# SensorU.net
KiCad netlist of a schematic drawn in EAGLE
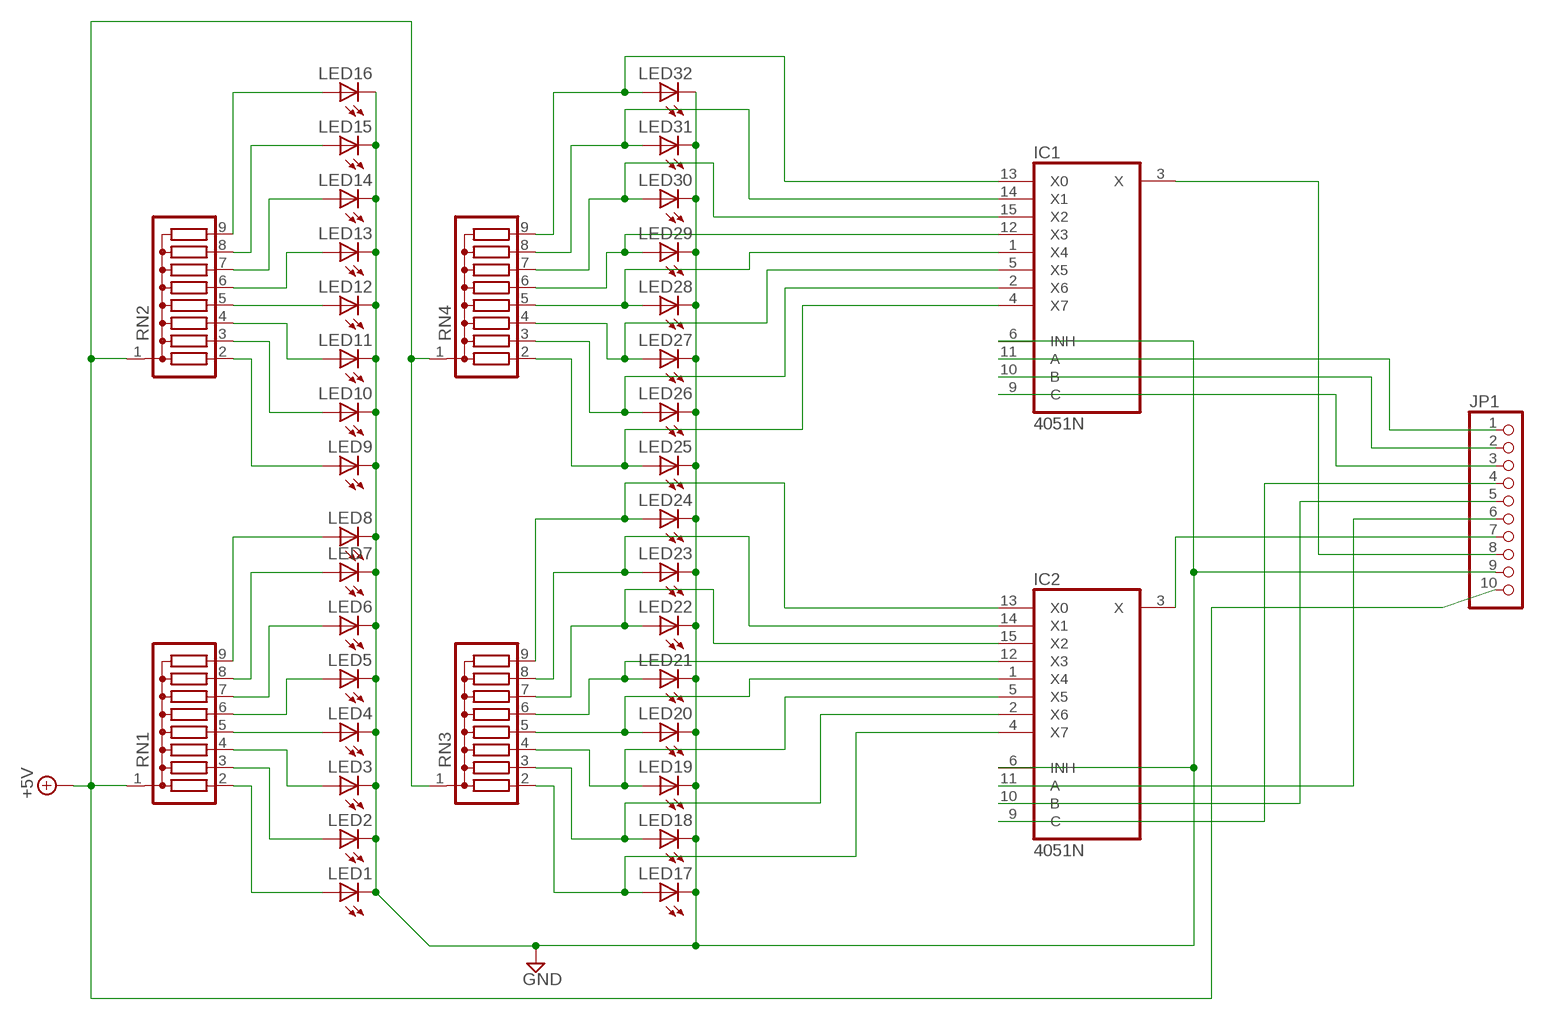
[diagram p0: schematic, sheet 1]

(export (version "E")
  (design (tool "Eeschema 10.0.6"))
  (components
    (comp (ref "IC1")
      (value "4051N")
      (footprint "eagle-import:DIL16")
      (libsource (lib "eagle-import") (part "4051N"))
    )
    (comp (ref "IC2")
      (value "4051N")
      (footprint "eagle-import:DIL16")
      (libsource (lib "eagle-import") (part "4051N"))
    )
    (comp (ref "JP1")
      (value "PINHD-1X10")
      (footprint "eagle-import:1X10")
      (libsource (lib "eagle-import") (part "PINHD-1X10"))
    )
    (comp (ref "LED1")
      (value "LED3MM")
      (footprint "eagle-import:LED3MM")
      (libsource (lib "eagle-import") (part "LED3MM"))
    )
    (comp (ref "LED2")
      (value "LED3MM")
      (footprint "eagle-import:LED3MM")
      (libsource (lib "eagle-import") (part "LED3MM"))
    )
    (comp (ref "LED3")
      (value "LED3MM")
      (footprint "eagle-import:LED3MM")
      (libsource (lib "eagle-import") (part "LED3MM"))
    )
    (comp (ref "LED4")
      (value "LED3MM")
      (footprint "eagle-import:LED3MM")
      (libsource (lib "eagle-import") (part "LED3MM"))
    )
    (comp (ref "LED5")
      (value "LED3MM")
      (footprint "eagle-import:LED3MM")
      (libsource (lib "eagle-import") (part "LED3MM"))
    )
    (comp (ref "LED6")
      (value "LED3MM")
      (footprint "eagle-import:LED3MM")
      (libsource (lib "eagle-import") (part "LED3MM"))
    )
    (comp (ref "LED7")
      (value "LED3MM")
      (footprint "eagle-import:LED3MM")
      (libsource (lib "eagle-import") (part "LED3MM"))
    )
    (comp (ref "LED8")
      (value "LED3MM")
      (footprint "eagle-import:LED3MM")
      (libsource (lib "eagle-import") (part "LED3MM"))
    )
    (comp (ref "LED9")
      (value "LED3MM")
      (footprint "eagle-import:LED3MM")
      (libsource (lib "eagle-import") (part "LED3MM"))
    )
    (comp (ref "LED10")
      (value "LED3MM")
      (footprint "eagle-import:LED3MM")
      (libsource (lib "eagle-import") (part "LED3MM"))
    )
    (comp (ref "LED11")
      (value "LED3MM")
      (footprint "eagle-import:LED3MM")
      (libsource (lib "eagle-import") (part "LED3MM"))
    )
    (comp (ref "LED12")
      (value "LED3MM")
      (footprint "eagle-import:LED3MM")
      (libsource (lib "eagle-import") (part "LED3MM"))
    )
    (comp (ref "LED13")
      (value "LED3MM")
      (footprint "eagle-import:LED3MM")
      (libsource (lib "eagle-import") (part "LED3MM"))
    )
    (comp (ref "LED14")
      (value "LED3MM")
      (footprint "eagle-import:LED3MM")
      (libsource (lib "eagle-import") (part "LED3MM"))
    )
    (comp (ref "LED15")
      (value "LED3MM")
      (footprint "eagle-import:LED3MM")
      (libsource (lib "eagle-import") (part "LED3MM"))
    )
    (comp (ref "LED16")
      (value "LED3MM")
      (footprint "eagle-import:LED3MM")
      (libsource (lib "eagle-import") (part "LED3MM"))
    )
    (comp (ref "LED17")
      (value "LED3MM")
      (footprint "eagle-import:LED3MM")
      (libsource (lib "eagle-import") (part "LED3MM"))
    )
    (comp (ref "LED18")
      (value "LED3MM")
      (footprint "eagle-import:LED3MM")
      (libsource (lib "eagle-import") (part "LED3MM"))
    )
    (comp (ref "LED19")
      (value "LED3MM")
      (footprint "eagle-import:LED3MM")
      (libsource (lib "eagle-import") (part "LED3MM"))
    )
    (comp (ref "LED20")
      (value "LED3MM")
      (footprint "eagle-import:LED3MM")
      (libsource (lib "eagle-import") (part "LED3MM"))
    )
    (comp (ref "LED21")
      (value "LED3MM")
      (footprint "eagle-import:LED3MM")
      (libsource (lib "eagle-import") (part "LED3MM"))
    )
    (comp (ref "LED22")
      (value "LED3MM")
      (footprint "eagle-import:LED3MM")
      (libsource (lib "eagle-import") (part "LED3MM"))
    )
    (comp (ref "LED23")
      (value "LED3MM")
      (footprint "eagle-import:LED3MM")
      (libsource (lib "eagle-import") (part "LED3MM"))
    )
    (comp (ref "LED24")
      (value "LED3MM")
      (footprint "eagle-import:LED3MM")
      (libsource (lib "eagle-import") (part "LED3MM"))
    )
    (comp (ref "LED25")
      (value "LED3MM")
      (footprint "eagle-import:LED3MM")
      (libsource (lib "eagle-import") (part "LED3MM"))
    )
    (comp (ref "LED26")
      (value "LED3MM")
      (footprint "eagle-import:LED3MM")
      (libsource (lib "eagle-import") (part "LED3MM"))
    )
    (comp (ref "LED27")
      (value "LED3MM")
      (footprint "eagle-import:LED3MM")
      (libsource (lib "eagle-import") (part "LED3MM"))
    )
    (comp (ref "LED28")
      (value "LED3MM")
      (footprint "eagle-import:LED3MM")
      (libsource (lib "eagle-import") (part "LED3MM"))
    )
    (comp (ref "LED29")
      (value "LED3MM")
      (footprint "eagle-import:LED3MM")
      (libsource (lib "eagle-import") (part "LED3MM"))
    )
    (comp (ref "LED30")
      (value "LED3MM")
      (footprint "eagle-import:LED3MM")
      (libsource (lib "eagle-import") (part "LED3MM"))
    )
    (comp (ref "LED31")
      (value "LED3MM")
      (footprint "eagle-import:LED3MM")
      (libsource (lib "eagle-import") (part "LED3MM"))
    )
    (comp (ref "LED32")
      (value "LED3MM")
      (footprint "eagle-import:LED3MM")
      (libsource (lib "eagle-import") (part "LED3MM"))
    )
    (comp (ref "RN1")
      (value "G08R")
      (footprint "eagle-import:SIL9")
      (libsource (lib "eagle-import") (part "G08R"))
    )
    (comp (ref "RN2")
      (value "G08R")
      (footprint "eagle-import:SIL9")
      (libsource (lib "eagle-import") (part "G08R"))
    )
    (comp (ref "RN3")
      (value "G08R")
      (footprint "eagle-import:SIL9")
      (libsource (lib "eagle-import") (part "G08R"))
    )
    (comp (ref "RN4")
      (value "G08R")
      (footprint "eagle-import:SIL9")
      (libsource (lib "eagle-import") (part "G08R"))
    )
  )
  (nets
    (net (code "1") (name "+5V") (class "Default")
      (node (ref "JP1") (pin "10") (pinfunction "10_10") (pintype "passive"))
      (node (ref "RN1") (pin "1") (pinfunction "1_1") (pintype "passive"))
      (node (ref "RN2") (pin "1") (pinfunction "1_1") (pintype "passive"))
      (node (ref "RN3") (pin "1") (pinfunction "1_1") (pintype "passive"))
      (node (ref "RN4") (pin "1") (pinfunction "1_1") (pintype "passive"))
    )
    (net (code "2") (name "GND") (class "Default")
      (node (ref "IC1") (pin "6") (pinfunction "INH_6") (pintype "input"))
      (node (ref "IC2") (pin "6") (pinfunction "INH_6") (pintype "input"))
      (node (ref "JP1") (pin "9") (pinfunction "9_9") (pintype "passive"))
      (node (ref "LED1") (pin "K") (pinfunction "C_K") (pintype "passive"))
      (node (ref "LED10") (pin "K") (pinfunction "C_K") (pintype "passive"))
      (node (ref "LED11") (pin "K") (pinfunction "C_K") (pintype "passive"))
      (node (ref "LED12") (pin "K") (pinfunction "C_K") (pintype "passive"))
      (node (ref "LED13") (pin "K") (pinfunction "C_K") (pintype "passive"))
      (node (ref "LED14") (pin "K") (pinfunction "C_K") (pintype "passive"))
      (node (ref "LED15") (pin "K") (pinfunction "C_K") (pintype "passive"))
      (node (ref "LED16") (pin "K") (pinfunction "C_K") (pintype "passive"))
      (node (ref "LED17") (pin "K") (pinfunction "C_K") (pintype "passive"))
      (node (ref "LED18") (pin "K") (pinfunction "C_K") (pintype "passive"))
      (node (ref "LED19") (pin "K") (pinfunction "C_K") (pintype "passive"))
      (node (ref "LED2") (pin "K") (pinfunction "C_K") (pintype "passive"))
      (node (ref "LED20") (pin "K") (pinfunction "C_K") (pintype "passive"))
      (node (ref "LED21") (pin "K") (pinfunction "C_K") (pintype "passive"))
      (node (ref "LED22") (pin "K") (pinfunction "C_K") (pintype "passive"))
      (node (ref "LED23") (pin "K") (pinfunction "C_K") (pintype "passive"))
      (node (ref "LED24") (pin "K") (pinfunction "C_K") (pintype "passive"))
      (node (ref "LED25") (pin "K") (pinfunction "C_K") (pintype "passive"))
      (node (ref "LED26") (pin "K") (pinfunction "C_K") (pintype "passive"))
      (node (ref "LED27") (pin "K") (pinfunction "C_K") (pintype "passive"))
      (node (ref "LED28") (pin "K") (pinfunction "C_K") (pintype "passive"))
      (node (ref "LED29") (pin "K") (pinfunction "C_K") (pintype "passive"))
      (node (ref "LED3") (pin "K") (pinfunction "C_K") (pintype "passive"))
      (node (ref "LED30") (pin "K") (pinfunction "C_K") (pintype "passive"))
      (node (ref "LED31") (pin "K") (pinfunction "C_K") (pintype "passive"))
      (node (ref "LED32") (pin "K") (pinfunction "C_K") (pintype "passive"))
      (node (ref "LED4") (pin "K") (pinfunction "C_K") (pintype "passive"))
      (node (ref "LED5") (pin "K") (pinfunction "C_K") (pintype "passive"))
      (node (ref "LED6") (pin "K") (pinfunction "C_K") (pintype "passive"))
      (node (ref "LED7") (pin "K") (pinfunction "C_K") (pintype "passive"))
      (node (ref "LED8") (pin "K") (pinfunction "C_K") (pintype "passive"))
      (node (ref "LED9") (pin "K") (pinfunction "C_K") (pintype "passive"))
    )
    (net (code "3") (name "Net-(IC1A-A)") (class "Default")
      (node (ref "IC1") (pin "11") (pinfunction "A_11") (pintype "input"))
      (node (ref "JP1") (pin "1") (pinfunction "1_1") (pintype "passive"))
    )
    (net (code "4") (name "Net-(IC1A-B)") (class "Default")
      (node (ref "IC1") (pin "10") (pinfunction "B_10") (pintype "input"))
      (node (ref "JP1") (pin "2") (pinfunction "2_2") (pintype "passive"))
    )
    (net (code "5") (name "Net-(IC1A-C)") (class "Default")
      (node (ref "IC1") (pin "9") (pinfunction "C_9") (pintype "input"))
      (node (ref "JP1") (pin "3") (pinfunction "3_3") (pintype "passive"))
    )
    (net (code "6") (name "Net-(IC1A-X)") (class "Default")
      (node (ref "IC1") (pin "3") (pinfunction "X_3") (pintype "bidirectional"))
      (node (ref "JP1") (pin "8") (pinfunction "8_8") (pintype "passive"))
    )
    (net (code "7") (name "Net-(IC1A-X0)") (class "Default")
      (node (ref "IC1") (pin "13") (pinfunction "X0_13") (pintype "bidirectional"))
      (node (ref "LED32") (pin "A") (pinfunction "A_A") (pintype "passive"))
      (node (ref "RN4") (pin "9") (pinfunction "9_9") (pintype "passive"))
    )
    (net (code "8") (name "Net-(IC1A-X1)") (class "Default")
      (node (ref "IC1") (pin "14") (pinfunction "X1_14") (pintype "bidirectional"))
      (node (ref "LED31") (pin "A") (pinfunction "A_A") (pintype "passive"))
      (node (ref "RN4") (pin "8") (pinfunction "8_8") (pintype "passive"))
    )
    (net (code "9") (name "Net-(IC1A-X2)") (class "Default")
      (node (ref "IC1") (pin "15") (pinfunction "X2_15") (pintype "bidirectional"))
      (node (ref "LED30") (pin "A") (pinfunction "A_A") (pintype "passive"))
      (node (ref "RN4") (pin "7") (pinfunction "7_7") (pintype "passive"))
    )
    (net (code "10") (name "Net-(IC1A-X3)") (class "Default")
      (node (ref "IC1") (pin "12") (pinfunction "X3_12") (pintype "bidirectional"))
      (node (ref "LED29") (pin "A") (pinfunction "A_A") (pintype "passive"))
      (node (ref "RN4") (pin "6") (pinfunction "6_6") (pintype "passive"))
    )
    (net (code "11") (name "Net-(IC1A-X4)") (class "Default")
      (node (ref "IC1") (pin "1") (pinfunction "X4_1") (pintype "bidirectional"))
      (node (ref "LED28") (pin "A") (pinfunction "A_A") (pintype "passive"))
      (node (ref "RN4") (pin "5") (pinfunction "5_5") (pintype "passive"))
    )
    (net (code "12") (name "Net-(IC1A-X5)") (class "Default")
      (node (ref "IC1") (pin "5") (pinfunction "X5_5") (pintype "bidirectional"))
      (node (ref "LED27") (pin "A") (pinfunction "A_A") (pintype "passive"))
      (node (ref "RN4") (pin "4") (pinfunction "4_4") (pintype "passive"))
    )
    (net (code "13") (name "Net-(IC1A-X6)") (class "Default")
      (node (ref "IC1") (pin "2") (pinfunction "X6_2") (pintype "bidirectional"))
      (node (ref "LED26") (pin "A") (pinfunction "A_A") (pintype "passive"))
      (node (ref "RN4") (pin "3") (pinfunction "3_3") (pintype "passive"))
    )
    (net (code "14") (name "Net-(IC1A-X7)") (class "Default")
      (node (ref "IC1") (pin "4") (pinfunction "X7_4") (pintype "bidirectional"))
      (node (ref "LED25") (pin "A") (pinfunction "A_A") (pintype "passive"))
      (node (ref "RN4") (pin "2") (pinfunction "2_2") (pintype "passive"))
    )
    (net (code "15") (name "Net-(IC2A-A)") (class "Default")
      (node (ref "IC2") (pin "11") (pinfunction "A_11") (pintype "input"))
      (node (ref "JP1") (pin "6") (pinfunction "6_6") (pintype "passive"))
    )
    (net (code "16") (name "Net-(IC2A-B)") (class "Default")
      (node (ref "IC2") (pin "10") (pinfunction "B_10") (pintype "input"))
      (node (ref "JP1") (pin "5") (pinfunction "5_5") (pintype "passive"))
    )
    (net (code "17") (name "Net-(IC2A-C)") (class "Default")
      (node (ref "IC2") (pin "9") (pinfunction "C_9") (pintype "input"))
      (node (ref "JP1") (pin "4") (pinfunction "4_4") (pintype "passive"))
    )
    (net (code "18") (name "Net-(IC2A-X)") (class "Default")
      (node (ref "IC2") (pin "3") (pinfunction "X_3") (pintype "bidirectional"))
      (node (ref "JP1") (pin "7") (pinfunction "7_7") (pintype "passive"))
    )
    (net (code "19") (name "Net-(IC2A-X0)") (class "Default")
      (node (ref "IC2") (pin "13") (pinfunction "X0_13") (pintype "bidirectional"))
      (node (ref "LED24") (pin "A") (pinfunction "A_A") (pintype "passive"))
      (node (ref "RN3") (pin "9") (pinfunction "9_9") (pintype "passive"))
    )
    (net (code "20") (name "Net-(IC2A-X1)") (class "Default")
      (node (ref "IC2") (pin "14") (pinfunction "X1_14") (pintype "bidirectional"))
      (node (ref "LED23") (pin "A") (pinfunction "A_A") (pintype "passive"))
      (node (ref "RN3") (pin "8") (pinfunction "8_8") (pintype "passive"))
    )
    (net (code "21") (name "Net-(IC2A-X2)") (class "Default")
      (node (ref "IC2") (pin "15") (pinfunction "X2_15") (pintype "bidirectional"))
      (node (ref "LED22") (pin "A") (pinfunction "A_A") (pintype "passive"))
      (node (ref "RN3") (pin "7") (pinfunction "7_7") (pintype "passive"))
    )
    (net (code "22") (name "Net-(IC2A-X3)") (class "Default")
      (node (ref "IC2") (pin "12") (pinfunction "X3_12") (pintype "bidirectional"))
      (node (ref "LED21") (pin "A") (pinfunction "A_A") (pintype "passive"))
      (node (ref "RN3") (pin "6") (pinfunction "6_6") (pintype "passive"))
    )
    (net (code "23") (name "Net-(IC2A-X4)") (class "Default")
      (node (ref "IC2") (pin "1") (pinfunction "X4_1") (pintype "bidirectional"))
      (node (ref "LED20") (pin "A") (pinfunction "A_A") (pintype "passive"))
      (node (ref "RN3") (pin "5") (pinfunction "5_5") (pintype "passive"))
    )
    (net (code "24") (name "Net-(IC2A-X5)") (class "Default")
      (node (ref "IC2") (pin "5") (pinfunction "X5_5") (pintype "bidirectional"))
      (node (ref "LED19") (pin "A") (pinfunction "A_A") (pintype "passive"))
      (node (ref "RN3") (pin "4") (pinfunction "4_4") (pintype "passive"))
    )
    (net (code "25") (name "Net-(IC2A-X6)") (class "Default")
      (node (ref "IC2") (pin "2") (pinfunction "X6_2") (pintype "bidirectional"))
      (node (ref "LED18") (pin "A") (pinfunction "A_A") (pintype "passive"))
      (node (ref "RN3") (pin "3") (pinfunction "3_3") (pintype "passive"))
    )
    (net (code "26") (name "Net-(IC2A-X7)") (class "Default")
      (node (ref "IC2") (pin "4") (pinfunction "X7_4") (pintype "bidirectional"))
      (node (ref "LED17") (pin "A") (pinfunction "A_A") (pintype "passive"))
      (node (ref "RN3") (pin "2") (pinfunction "2_2") (pintype "passive"))
    )
    (net (code "27") (name "Net-(LED1-PadA)") (class "Default")
      (node (ref "LED1") (pin "A") (pinfunction "A_A") (pintype "passive"))
      (node (ref "RN1") (pin "2") (pinfunction "2_2") (pintype "passive"))
    )
    (net (code "28") (name "Net-(LED2-PadA)") (class "Default")
      (node (ref "LED2") (pin "A") (pinfunction "A_A") (pintype "passive"))
      (node (ref "RN1") (pin "3") (pinfunction "3_3") (pintype "passive"))
    )
    (net (code "29") (name "Net-(LED3-PadA)") (class "Default")
      (node (ref "LED3") (pin "A") (pinfunction "A_A") (pintype "passive"))
      (node (ref "RN1") (pin "4") (pinfunction "4_4") (pintype "passive"))
    )
    (net (code "30") (name "Net-(LED4-PadA)") (class "Default")
      (node (ref "LED4") (pin "A") (pinfunction "A_A") (pintype "passive"))
      (node (ref "RN1") (pin "5") (pinfunction "5_5") (pintype "passive"))
    )
    (net (code "31") (name "Net-(LED5-PadA)") (class "Default")
      (node (ref "LED5") (pin "A") (pinfunction "A_A") (pintype "passive"))
      (node (ref "RN1") (pin "6") (pinfunction "6_6") (pintype "passive"))
    )
    (net (code "32") (name "Net-(LED6-PadA)") (class "Default")
      (node (ref "LED6") (pin "A") (pinfunction "A_A") (pintype "passive"))
      (node (ref "RN1") (pin "7") (pinfunction "7_7") (pintype "passive"))
    )
    (net (code "33") (name "Net-(LED7-PadA)") (class "Default")
      (node (ref "LED7") (pin "A") (pinfunction "A_A") (pintype "passive"))
      (node (ref "RN1") (pin "8") (pinfunction "8_8") (pintype "passive"))
    )
    (net (code "34") (name "Net-(LED8-PadA)") (class "Default")
      (node (ref "LED8") (pin "A") (pinfunction "A_A") (pintype "passive"))
      (node (ref "RN1") (pin "9") (pinfunction "9_9") (pintype "passive"))
    )
    (net (code "35") (name "Net-(LED9-PadA)") (class "Default")
      (node (ref "LED9") (pin "A") (pinfunction "A_A") (pintype "passive"))
      (node (ref "RN2") (pin "2") (pinfunction "2_2") (pintype "passive"))
    )
    (net (code "36") (name "Net-(LED10-PadA)") (class "Default")
      (node (ref "LED10") (pin "A") (pinfunction "A_A") (pintype "passive"))
      (node (ref "RN2") (pin "3") (pinfunction "3_3") (pintype "passive"))
    )
    (net (code "37") (name "Net-(LED11-PadA)") (class "Default")
      (node (ref "LED11") (pin "A") (pinfunction "A_A") (pintype "passive"))
      (node (ref "RN2") (pin "4") (pinfunction "4_4") (pintype "passive"))
    )
    (net (code "38") (name "Net-(LED12-PadA)") (class "Default")
      (node (ref "LED12") (pin "A") (pinfunction "A_A") (pintype "passive"))
      (node (ref "RN2") (pin "5") (pinfunction "5_5") (pintype "passive"))
    )
    (net (code "39") (name "Net-(LED13-PadA)") (class "Default")
      (node (ref "LED13") (pin "A") (pinfunction "A_A") (pintype "passive"))
      (node (ref "RN2") (pin "6") (pinfunction "6_6") (pintype "passive"))
    )
    (net (code "40") (name "Net-(LED14-PadA)") (class "Default")
      (node (ref "LED14") (pin "A") (pinfunction "A_A") (pintype "passive"))
      (node (ref "RN2") (pin "7") (pinfunction "7_7") (pintype "passive"))
    )
    (net (code "41") (name "Net-(LED15-PadA)") (class "Default")
      (node (ref "LED15") (pin "A") (pinfunction "A_A") (pintype "passive"))
      (node (ref "RN2") (pin "8") (pinfunction "8_8") (pintype "passive"))
    )
    (net (code "42") (name "Net-(LED16-PadA)") (class "Default")
      (node (ref "LED16") (pin "A") (pinfunction "A_A") (pintype "passive"))
      (node (ref "RN2") (pin "9") (pinfunction "9_9") (pintype "passive"))
    )
  )
)
